# LB_BIT_i11_PRESSURESENSOR-v02_rev1.net
KiCad netlist of a schematic drawn in EAGLE
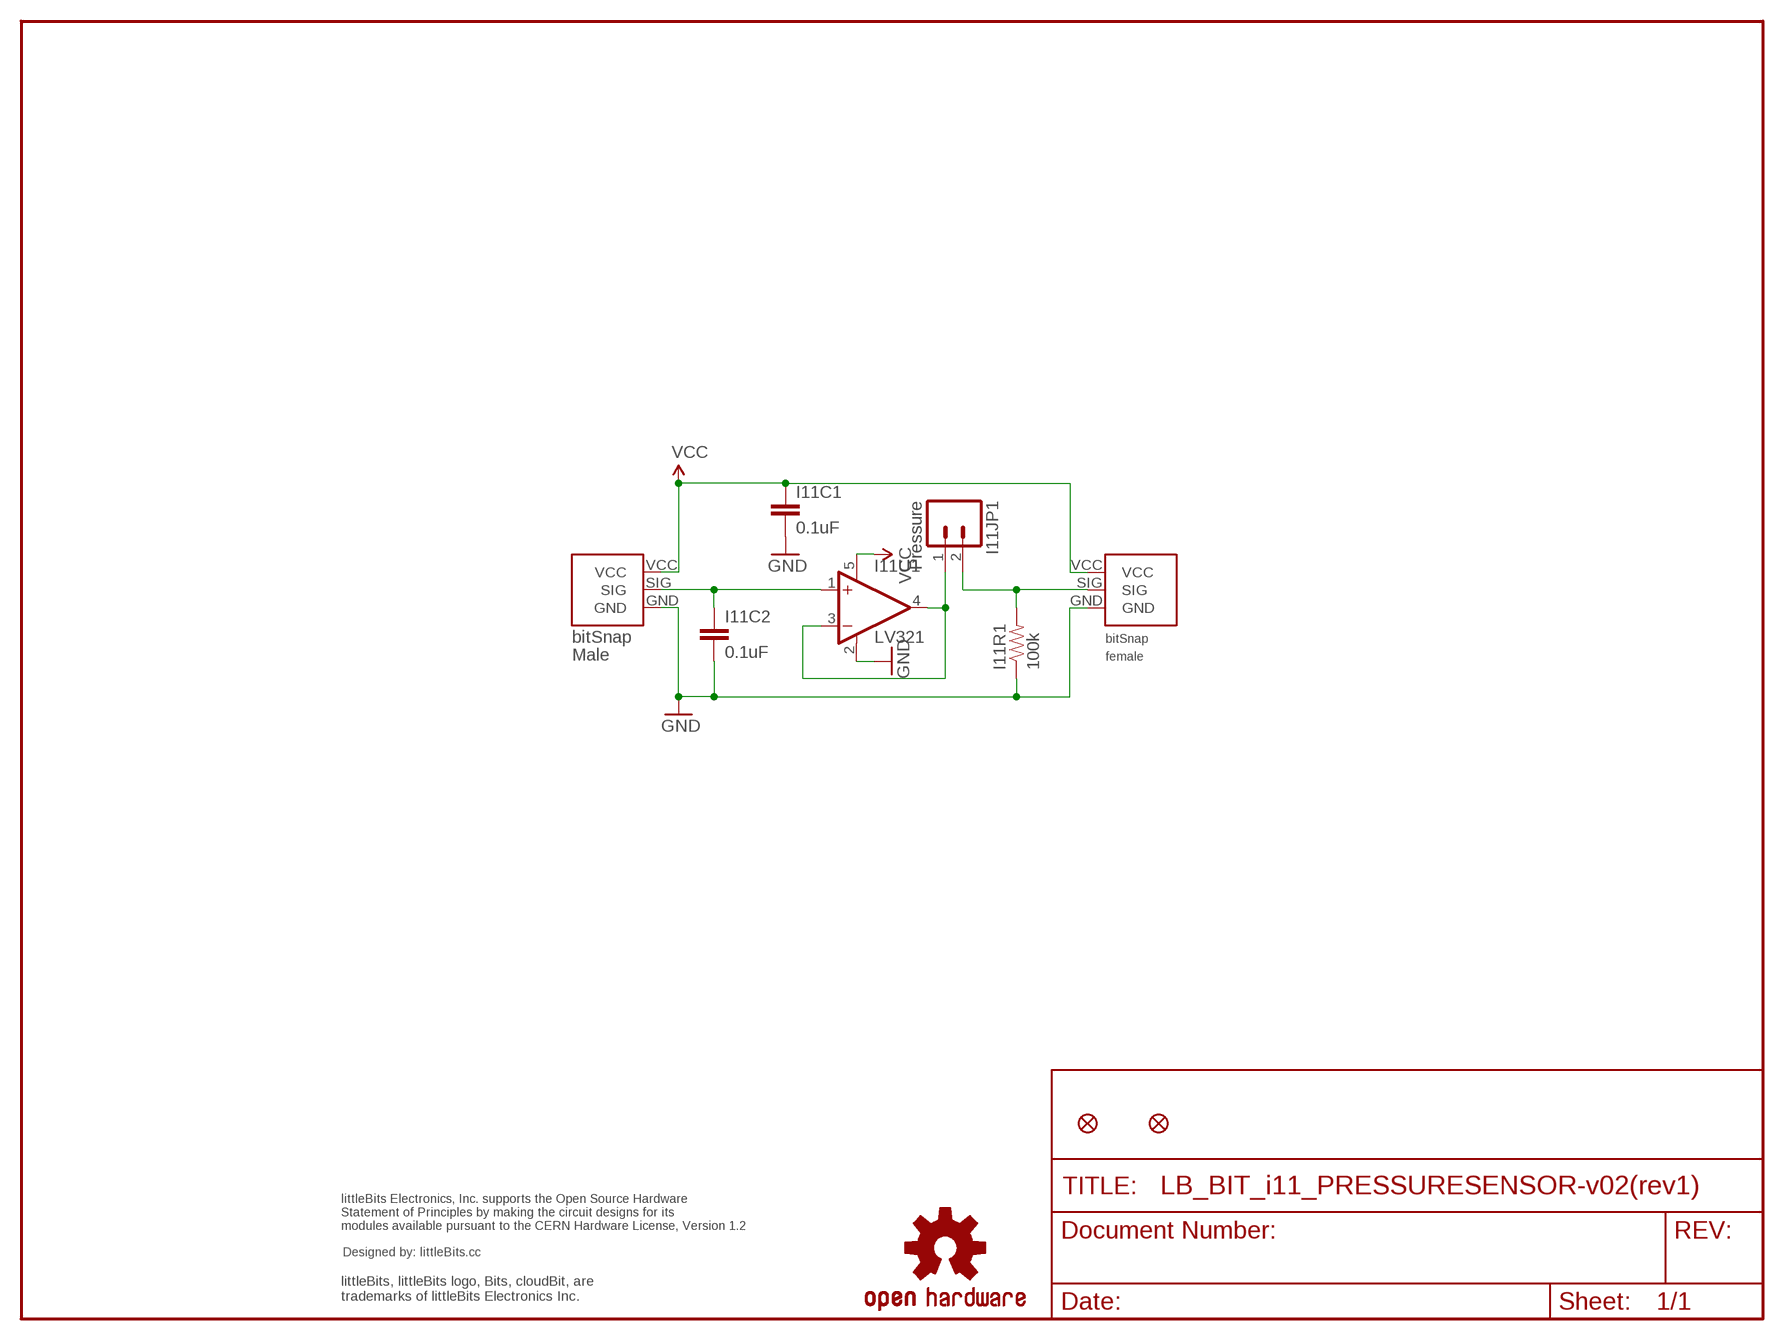
[diagram p0: schematic, sheet 1]

(export (version "E")
  (design (tool "Eeschema 10.0.6"))
  (components
    (comp (ref "I11BSF")
      (value "BITSNAP_FEMALE")
      (footprint "eagle-import:BITSNAP_FEMALE")
      (libsource (lib "eagle-import") (part "BITSNAP_FEMALE"))
    )
    (comp (ref "I11BSM")
      (value "BITSNAP_MALE")
      (footprint "eagle-import:BITSNAP_MALE")
      (libsource (lib "eagle-import") (part "BITSNAP_MALE"))
    )
    (comp (ref "I11C1")
      (value "0.1uF")
      (footprint "eagle-import:0603-CAP")
      (libsource (lib "eagle-import") (part "CAP0603-CAP"))
    )
    (comp (ref "I11C2")
      (value "0.1uF")
      (footprint "eagle-import:0603-CAP")
      (libsource (lib "eagle-import") (part "CAP0603-CAP"))
    )
    (comp (ref "I11JP1")
      (value "Pressure")
      (footprint "eagle-import:1X02")
      (libsource (lib "eagle-import") (part "M02PTH"))
    )
    (comp (ref "I11R1")
      (value "100k")
      (footprint "eagle-import:0603-RES")
      (libsource (lib "eagle-import") (part "RESISTOR0603-RES"))
    )
    (comp (ref "I11U1")
      (value "LV321")
      (footprint "eagle-import:SC70-5")
      (libsource (lib "eagle-import") (part "LV321"))
    )
    (comp (ref "JP2")
      (value "FIDUCIAL1X2.5")
      (footprint "eagle-import:FIDUCIAL-1X2.5")
      (libsource (lib "eagle-import") (part "FIDUCIAL1X2.5"))
    )
    (comp (ref "JP3")
      (value "FIDUCIAL1X2.5")
      (footprint "eagle-import:FIDUCIAL-1X2.5")
      (libsource (lib "eagle-import") (part "FIDUCIAL1X2.5"))
    )
    (comp (ref "U$1")
      (value "OSHWCREDIT")
      (footprint "eagle-import:OSHWCREDIT")
      (libsource (lib "eagle-import") (part "OSHWCREDIT"))
    )
    (comp (ref "U$4")
      (value "OSHW-LOGOL")
      (footprint "eagle-import:OSHW-LOGO-L")
      (libsource (lib "eagle-import") (part "OSHW-LOGOL"))
    )
  )
  (nets
    (net (code "1") (name "GND") (class "Default")
      (node (ref "I11BSF") (pin "GND") (pinfunction "GND_GND") (pintype "bidirectional"))
      (node (ref "I11BSM") (pin "GND") (pinfunction "GND_GND") (pintype "bidirectional"))
      (node (ref "I11C1") (pin "2") (pinfunction "2_2") (pintype "passive"))
      (node (ref "I11C2") (pin "2") (pinfunction "2_2") (pintype "passive"))
      (node (ref "I11R1") (pin "1") (pinfunction "1_1") (pintype "passive"))
      (node (ref "I11U1") (pin "2") (pinfunction "V-_2") (pintype "power_in"))
    )
    (net (code "2") (name "Net-(I11BSF-PadSIG)") (class "Default")
      (node (ref "I11BSF") (pin "SIG") (pinfunction "SIG_SIG") (pintype "bidirectional"))
      (node (ref "I11JP1") (pin "2") (pinfunction "2_2") (pintype "passive"))
      (node (ref "I11R1") (pin "2") (pinfunction "2_2") (pintype "passive"))
    )
    (net (code "3") (name "Net-(I11U1-+IN)") (class "Default")
      (node (ref "I11BSM") (pin "SIG") (pinfunction "SIG_SIG") (pintype "bidirectional"))
      (node (ref "I11C2") (pin "1") (pinfunction "1_1") (pintype "passive"))
      (node (ref "I11U1") (pin "1") (pinfunction "+IN_1") (pintype "input"))
    )
    (net (code "4") (name "Net-(I11U1--IN)") (class "Default")
      (node (ref "I11JP1") (pin "1") (pinfunction "1_1") (pintype "passive"))
      (node (ref "I11U1") (pin "3") (pinfunction "-IN_3") (pintype "input"))
      (node (ref "I11U1") (pin "4") (pinfunction "OUT_4") (pintype "output"))
    )
    (net (code "5") (name "VCC") (class "Default")
      (node (ref "I11BSF") (pin "VCC") (pinfunction "VCC_VCC") (pintype "bidirectional"))
      (node (ref "I11BSM") (pin "VCC") (pinfunction "VCC_VCC") (pintype "bidirectional"))
      (node (ref "I11C1") (pin "1") (pinfunction "1_1") (pintype "passive"))
      (node (ref "I11U1") (pin "5") (pinfunction "V+_5") (pintype "power_in"))
    )
  )
)
